# Vorlage_ATmega644PA.net
KiCad netlist of a schematic drawn in EAGLE
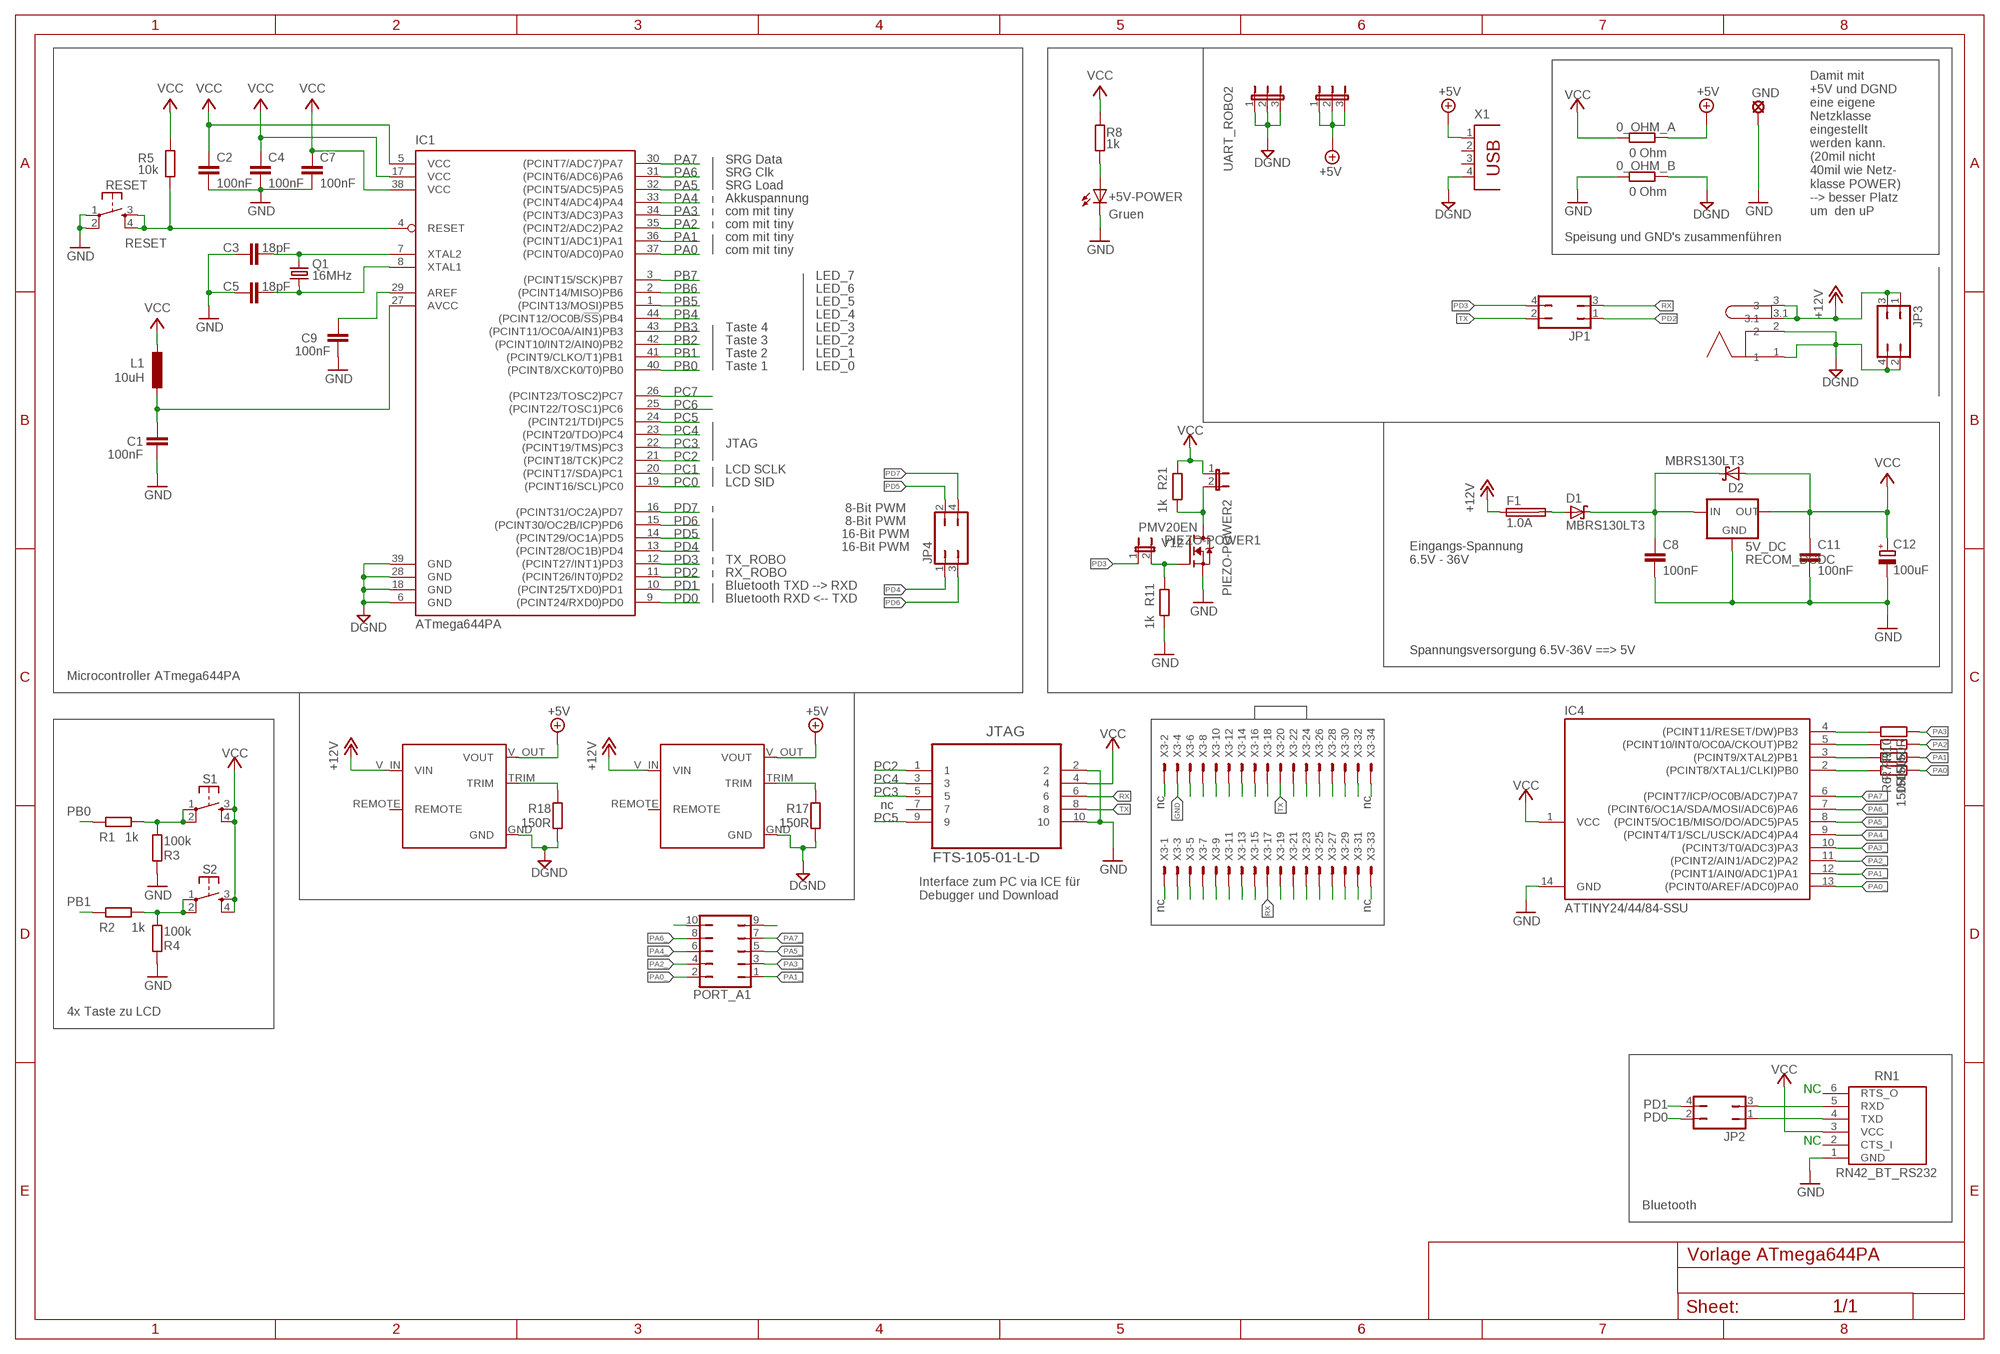
[diagram p0: schematic, sheet 1]

(export (version "E")
  (design (tool "Eeschema 10.0.6"))
  (components
    (comp (ref "+5V-POWER")
      (value "Gruen")
      (footprint "eagle-import:CHIPLED_1206")
      (libsource (lib "eagle-import") (part "LEDCHIPLED_1206"))
    )
    (comp (ref "0_OHM_A")
      (value "0 Ohm")
      (footprint "eagle-import:R0805")
      (libsource (lib "eagle-import") (part "rcl_334_R-EU_R0805"))
    )
    (comp (ref "0_OHM_B")
      (value "0 Ohm")
      (footprint "eagle-import:R0805")
      (libsource (lib "eagle-import") (part "rcl_334_R-EU_R0805"))
    )
    (comp (ref "5V_DC")
      (value "RECOM_DCDC")
      (footprint "eagle-import:RECOM_DCDC")
      (libsource (lib "eagle-import") (part "RECOM_DCDC"))
    )
    (comp (ref "C1")
      (value "100nF")
      (footprint "eagle-import:C0805")
      (libsource (lib "eagle-import") (part "C-EUC0805"))
    )
    (comp (ref "C2")
      (value "100nF")
      (footprint "eagle-import:C0805")
      (libsource (lib "eagle-import") (part "C-EUC0805"))
    )
    (comp (ref "C3")
      (value "18pF")
      (footprint "eagle-import:C0805")
      (libsource (lib "eagle-import") (part "C-EUC0805"))
    )
    (comp (ref "C4")
      (value "100nF")
      (footprint "eagle-import:C0805")
      (libsource (lib "eagle-import") (part "C-EUC0805"))
    )
    (comp (ref "C5")
      (value "18pF")
      (footprint "eagle-import:C0805")
      (libsource (lib "eagle-import") (part "C-EUC0805"))
    )
    (comp (ref "C7")
      (value "100nF")
      (footprint "eagle-import:C0805")
      (libsource (lib "eagle-import") (part "C-EUC0805"))
    )
    (comp (ref "C8")
      (value "100nF")
      (footprint "eagle-import:C0805")
      (libsource (lib "eagle-import") (part "C-EUC0805"))
    )
    (comp (ref "C9")
      (value "100nF")
      (footprint "eagle-import:C0805")
      (libsource (lib "eagle-import") (part "C-EUC0805"))
    )
    (comp (ref "C11")
      (value "100nF")
      (footprint "eagle-import:C0805")
      (libsource (lib "eagle-import") (part "C-EUC0805"))
    )
    (comp (ref "C12")
      (value "100uF")
      (footprint "eagle-import:UD-6,3X5,8_NICHICON")
      (libsource (lib "eagle-import") (part "CPOL-EUUD-6,3X8,8"))
    )
    (comp (ref "D1")
      (value "MBRS130LT3")
      (footprint "eagle-import:SMB")
      (libsource (lib "eagle-import") (part "MBRS130LT3"))
    )
    (comp (ref "D2")
      (value "MBRS130LT3")
      (footprint "eagle-import:SMB")
      (libsource (lib "eagle-import") (part "MBRS130LT3"))
    )
    (comp (ref "F1")
      (value "1.0A")
      (footprint "eagle-import:F1206")
      (libsource (lib "eagle-import") (part "195601206"))
    )
    (comp (ref "GND")
      (value "3.3V")
      (footprint "eagle-import:LSP11")
      (libsource (lib "eagle-import") (part "LSP11"))
    )
    (comp (ref "IC1")
      (value "ATmega644PA")
      (footprint "eagle-import:TQFP44")
      (fields (field (name "MPN") "ATMEGA644PV-10AU"))
      (libsource (lib "eagle-import") (part "ATMEGA644A"))
    )
    (comp (ref "IC4")
      (value "ATTINY24/44/84-SSU")
      (footprint "eagle-import:SOIC14")
      (libsource (lib "eagle-import") (part "ATTINY24/44/84-SSU"))
    )
    (comp (ref "JP1")
      (value "JP2Q")
      (footprint "eagle-import:JP2Q")
      (libsource (lib "eagle-import") (part "JP2Q"))
    )
    (comp (ref "JP2")
      (value "JP2Q")
      (footprint "eagle-import:JP2Q")
      (libsource (lib "eagle-import") (part "JP2Q"))
    )
    (comp (ref "JP3")
      (value "JP2Q")
      (footprint "eagle-import:JP2Q")
      (libsource (lib "eagle-import") (part "JP2Q"))
    )
    (comp (ref "JP4")
      (value "JP2Q")
      (footprint "eagle-import:JP2Q")
      (libsource (lib "eagle-import") (part "JP2Q"))
    )
    (comp (ref "JTAG")
      (value "FTS-105-01-L-D")
      (footprint "eagle-import:SAMTEC_FTS-105-01-L-D")
      (libsource (lib "eagle-import") (part "FTS-105-01-L-D"))
    )
    (comp (ref "L1")
      (value "10uH")
      (footprint "eagle-import:L2825P")
      (libsource (lib "eagle-import") (part "L-EUL2825P"))
    )
    (comp (ref "PIEZO-POWER1")
      (value "JP1E")
      (footprint "eagle-import:JP1")
      (libsource (lib "eagle-import") (part "JP1E"))
    )
    (comp (ref "PIEZO-POWER2")
      (value "JP1E")
      (footprint "eagle-import:JP1")
      (libsource (lib "eagle-import") (part "JP1E"))
    )
    (comp (ref "PORT_A1")
      (value "JP5Q")
      (footprint "eagle-import:JP5Q")
      (libsource (lib "eagle-import") (part "JP5Q"))
    )
    (comp (ref "Q1")
      (value "16MHz")
      (footprint "eagle-import:HC49UP")
      (libsource (lib "eagle-import") (part "CRYSTALHC49UP"))
    )
    (comp (ref "R1")
      (value "1k")
      (footprint "eagle-import:R0805")
      (libsource (lib "eagle-import") (part "rcl_334_R-EU_R0805"))
    )
    (comp (ref "R2")
      (value "1k")
      (footprint "eagle-import:R0805")
      (libsource (lib "eagle-import") (part "rcl_334_R-EU_R0805"))
    )
    (comp (ref "R3")
      (value "100k")
      (footprint "eagle-import:R0805")
      (libsource (lib "eagle-import") (part "rcl_334_R-EU_R0805"))
    )
    (comp (ref "R4")
      (value "100k")
      (footprint "eagle-import:R0805")
      (libsource (lib "eagle-import") (part "rcl_334_R-EU_R0805"))
    )
    (comp (ref "R5")
      (value "10k")
      (footprint "eagle-import:R0805")
      (libsource (lib "eagle-import") (part "rcl_334_R-EU_R0805"))
    )
    (comp (ref "R6")
      (value "150R")
      (footprint "eagle-import:R0805")
      (libsource (lib "eagle-import") (part "rcl_334_R-EU_R0805"))
    )
    (comp (ref "R7")
      (value "150R")
      (footprint "eagle-import:R0805")
      (libsource (lib "eagle-import") (part "rcl_334_R-EU_R0805"))
    )
    (comp (ref "R8")
      (value "1k")
      (footprint "eagle-import:R0805")
      (libsource (lib "eagle-import") (part "rcl_334_R-EU_R0805"))
    )
    (comp (ref "R9")
      (value "150R")
      (footprint "eagle-import:R0805")
      (libsource (lib "eagle-import") (part "rcl_334_R-EU_R0805"))
    )
    (comp (ref "R10")
      (value "150R")
      (footprint "eagle-import:R0805")
      (libsource (lib "eagle-import") (part "rcl_334_R-EU_R0805"))
    )
    (comp (ref "R11")
      (value "1k")
      (footprint "eagle-import:R1206")
      (libsource (lib "eagle-import") (part "R-EU_R1206"))
    )
    (comp (ref "R17")
      (value "150R")
      (footprint "eagle-import:R0805")
      (libsource (lib "eagle-import") (part "rcl_334_R-EU_R0805"))
    )
    (comp (ref "R18")
      (value "150R")
      (footprint "eagle-import:R0805")
      (libsource (lib "eagle-import") (part "rcl_334_R-EU_R0805"))
    )
    (comp (ref "R21")
      (value "1k")
      (footprint "eagle-import:R1206")
      (libsource (lib "eagle-import") (part "R-EU_R1206"))
    )
    (comp (ref "RESET")
      (value "TS42_4PAD")
      (footprint "eagle-import:TS42_4PAD")
      (libsource (lib "eagle-import") (part "TS42_4PAD"))
    )
    (comp (ref "RN1")
      (value "RN42_BT_RS232")
      (footprint "eagle-import:RN42BT_RS232")
      (libsource (lib "eagle-import") (part "RN42_BT_RS232"))
    )
    (comp (ref "S1")
      (value "TS42_4PAD")
      (footprint "eagle-import:TS42_4PAD")
      (libsource (lib "eagle-import") (part "TS42_4PAD"))
    )
    (comp (ref "S2")
      (value "TS42_4PAD")
      (footprint "eagle-import:TS42_4PAD")
      (libsource (lib "eagle-import") (part "TS42_4PAD"))
    )
    (comp (ref "U$1")
      (value "BUCHSE")
      (footprint "eagle-import:BUCHSE")
      (libsource (lib "eagle-import") (part "BUCHSE"))
    )
    (comp (ref "U$2")
      (value "DCDC")
      (footprint "eagle-import:1X2,3_2.54MM")
      (libsource (lib "eagle-import") (part "DCDC"))
    )
    (comp (ref "U$3")
      (value "DCDC")
      (footprint "eagle-import:1X2,3_2.54MM")
      (libsource (lib "eagle-import") (part "DCDC"))
    )
    (comp (ref "UART_ROBO1")
      (value "JP2E")
      (footprint "eagle-import:JP2")
      (libsource (lib "eagle-import") (part "JP2E"))
    )
    (comp (ref "UART_ROBO2")
      (value "JP2E")
      (footprint "eagle-import:JP2")
      (libsource (lib "eagle-import") (part "JP2E"))
    )
    (comp (ref "V12")
      (value "PMV20EN")
      (footprint "eagle-import:SOT23")
      (libsource (lib "eagle-import") (part "BSS138"))
    )
    (comp (ref "X1")
      (value "PN87520")
      (footprint "eagle-import:PN87520")
      (libsource (lib "eagle-import") (part "PN87520"))
    )
    (comp (ref "X3")
      (value "87758-3416")
      (footprint "eagle-import:87758-3416")
      (fields (field (name "MF") "MOLEX"))
      (libsource (lib "eagle-import") (part "87758-3416"))
    )
  )
  (nets
    (net (code "1") (name "+5V") (class "Default")
      (node (ref "0_OHM_A") (pin "2") (pinfunction "2_2") (pintype "passive"))
      (node (ref "U$2") (pin "V_OUT") (pinfunction "VOUT_V_OUT") (pintype "bidirectional"))
      (node (ref "U$3") (pin "V_OUT") (pinfunction "VOUT_V_OUT") (pintype "bidirectional"))
      (node (ref "UART_ROBO1") (pin "1") (pinfunction "1_1") (pintype "passive"))
      (node (ref "UART_ROBO1") (pin "2") (pinfunction "2_2") (pintype "passive"))
      (node (ref "UART_ROBO1") (pin "3") (pinfunction "3_3") (pintype "passive"))
      (node (ref "X1") (pin "1") (pinfunction "1_1") (pintype "passive"))
    )
    (net (code "2") (name "+12V") (class "Default")
      (node (ref "F1") (pin "1") (pinfunction "1_1") (pintype "passive"))
      (node (ref "JP3") (pin "1") (pinfunction "1_1") (pintype "passive"))
      (node (ref "JP3") (pin "3") (pinfunction "3_3") (pintype "passive"))
      (node (ref "U$1") (pin "3") (pinfunction "3_3") (pintype "bidirectional"))
      (node (ref "U$1") (pin "3.1") (pinfunction "3.1_3.1") (pintype "bidirectional"))
      (node (ref "U$2") (pin "V_IN") (pinfunction "VIN_V_IN") (pintype "bidirectional"))
      (node (ref "U$3") (pin "V_IN") (pinfunction "VIN_V_IN") (pintype "bidirectional"))
    )
    (net (code "3") (name "/PA4") (class "Default")
      (node (ref "IC1") (pin "33") (pinfunction "(PCINT4/ADC4)PA4_33") (pintype "bidirectional"))
    )
    (net (code "4") (name "/PA5") (class "Default")
      (node (ref "IC1") (pin "32") (pinfunction "(PCINT5/ADC5)PA5_32") (pintype "bidirectional"))
    )
    (net (code "5") (name "/PA6") (class "Default")
      (node (ref "IC1") (pin "31") (pinfunction "(PCINT6/ADC6)PA6_31") (pintype "bidirectional"))
    )
    (net (code "6") (name "/PA7") (class "Default")
      (node (ref "IC1") (pin "30") (pinfunction "(PCINT7/ADC7)PA7_30") (pintype "bidirectional"))
    )
    (net (code "7") (name "/PB0") (class "Default")
      (node (ref "IC1") (pin "40") (pinfunction "(PCINT8/XCK0/T0)PB0_40") (pintype "bidirectional"))
      (node (ref "R1") (pin "1") (pinfunction "1_1") (pintype "passive"))
    )
    (net (code "8") (name "/PB1") (class "Default")
      (node (ref "IC1") (pin "41") (pinfunction "(PCINT9/CLKO/T1)PB1_41") (pintype "bidirectional"))
      (node (ref "R2") (pin "1") (pinfunction "1_1") (pintype "passive"))
    )
    (net (code "9") (name "/PB2") (class "Default")
      (node (ref "IC1") (pin "42") (pinfunction "(PCINT10/INT2/AIN0)PB2_42") (pintype "bidirectional"))
    )
    (net (code "10") (name "/PB3") (class "Default")
      (node (ref "IC1") (pin "43") (pinfunction "(PCINT11/OC0A/AIN1)PB3_43") (pintype "bidirectional"))
    )
    (net (code "11") (name "/PB4") (class "Default")
      (node (ref "IC1") (pin "44") (pinfunction "(PCINT12/OC0B/~{SS})PB4_44") (pintype "bidirectional"))
    )
    (net (code "12") (name "/PB5") (class "Default")
      (node (ref "IC1") (pin "1") (pinfunction "(PCINT13/MOSI)PB5_1") (pintype "bidirectional"))
    )
    (net (code "13") (name "/PB6") (class "Default")
      (node (ref "IC1") (pin "2") (pinfunction "(PCINT14/MISO)PB6_2") (pintype "bidirectional"))
    )
    (net (code "14") (name "/PB7") (class "Default")
      (node (ref "IC1") (pin "3") (pinfunction "(PCINT15/SCK)PB7_3") (pintype "bidirectional"))
    )
    (net (code "15") (name "/PC0") (class "Default")
      (node (ref "IC1") (pin "19") (pinfunction "(PCINT16/SCL)PC0_19") (pintype "output"))
    )
    (net (code "16") (name "/PC1") (class "Default")
      (node (ref "IC1") (pin "20") (pinfunction "(PCINT17/SDA)PC1_20") (pintype "output"))
    )
    (net (code "17") (name "/PC2") (class "Default")
      (node (ref "IC1") (pin "21") (pinfunction "(PCINT18/TCK)PC2_21") (pintype "output"))
      (node (ref "JTAG") (pin "1") (pinfunction "1_1") (pintype "passive"))
    )
    (net (code "18") (name "/PC3") (class "Default")
      (node (ref "IC1") (pin "22") (pinfunction "(PCINT19/TMS)PC3_22") (pintype "output"))
      (node (ref "JTAG") (pin "5") (pinfunction "5_5") (pintype "passive"))
    )
    (net (code "19") (name "/PC4") (class "Default")
      (node (ref "IC1") (pin "23") (pinfunction "(PCINT20/TDO)PC4_23") (pintype "output"))
      (node (ref "JTAG") (pin "3") (pinfunction "3_3") (pintype "passive"))
    )
    (net (code "20") (name "/PC5") (class "Default")
      (node (ref "IC1") (pin "24") (pinfunction "(PCINT21/TDI)PC5_24") (pintype "output"))
      (node (ref "JTAG") (pin "9") (pinfunction "9_9") (pintype "passive"))
    )
    (net (code "21") (name "/PC6") (class "Default")
      (node (ref "IC1") (pin "25") (pinfunction "(PCINT22/TOSC1)PC6_25") (pintype "output"))
    )
    (net (code "22") (name "/PC7") (class "Default")
      (node (ref "IC1") (pin "26") (pinfunction "(PCINT23/TOSC2)PC7_26") (pintype "output"))
    )
    (net (code "23") (name "/PD0") (class "Default")
      (node (ref "IC1") (pin "9") (pinfunction "(PCINT24/RXD0)PD0_9") (pintype "bidirectional"))
      (node (ref "JP2") (pin "2") (pinfunction "2_2") (pintype "passive"))
    )
    (net (code "24") (name "/PD1") (class "Default")
      (node (ref "IC1") (pin "10") (pinfunction "(PCINT25/TXD0)PD1_10") (pintype "bidirectional"))
      (node (ref "JP2") (pin "4") (pinfunction "4_4") (pintype "passive"))
    )
    (net (code "25") (name "/RESET") (class "Default")
      (node (ref "IC1") (pin "4") (pinfunction "RESET_4") (pintype "input"))
      (node (ref "R5") (pin "1") (pinfunction "1_1") (pintype "passive"))
      (node (ref "RESET") (pin "3") (pinfunction "3_3") (pintype "passive"))
      (node (ref "RESET") (pin "4") (pinfunction "4_4") (pintype "passive"))
    )
    (net (code "26") (name "DGND") (class "Default")
      (node (ref "0_OHM_B") (pin "2") (pinfunction "2_2") (pintype "passive"))
      (node (ref "IC1") (pin "18") (pinfunction "GND_18") (pintype "power_in"))
      (node (ref "IC1") (pin "28") (pinfunction "GND_28") (pintype "power_in"))
      (node (ref "IC1") (pin "39") (pinfunction "GND_39") (pintype "power_in"))
      (node (ref "IC1") (pin "6") (pinfunction "GND_6") (pintype "power_in"))
      (node (ref "JP3") (pin "2") (pinfunction "2_2") (pintype "passive"))
      (node (ref "JP3") (pin "4") (pinfunction "4_4") (pintype "passive"))
      (node (ref "R17") (pin "1") (pinfunction "1_1") (pintype "passive"))
      (node (ref "R18") (pin "1") (pinfunction "1_1") (pintype "passive"))
      (node (ref "U$1") (pin "1") (pinfunction "1_1") (pintype "bidirectional"))
      (node (ref "U$1") (pin "2") (pinfunction "2_2") (pintype "bidirectional"))
      (node (ref "U$2") (pin "GND") (pinfunction "GND_GND") (pintype "bidirectional"))
      (node (ref "U$3") (pin "GND") (pinfunction "GND_GND") (pintype "bidirectional"))
      (node (ref "UART_ROBO2") (pin "1") (pinfunction "1_1") (pintype "passive"))
      (node (ref "UART_ROBO2") (pin "2") (pinfunction "2_2") (pintype "passive"))
      (node (ref "UART_ROBO2") (pin "3") (pinfunction "3_3") (pintype "passive"))
      (node (ref "X1") (pin "4") (pinfunction "4_4") (pintype "passive"))
    )
    (net (code "27") (name "GND") (class "Default")
      (node (ref "+5V-POWER") (pin "C") (pinfunction "C_C") (pintype "passive"))
      (node (ref "0_OHM_B") (pin "1") (pinfunction "1_1") (pintype "passive"))
      (node (ref "5V_DC") (pin "GND") (pinfunction "GND_GND") (pintype "input"))
      (node (ref "C1") (pin "1") (pinfunction "1_1") (pintype "passive"))
      (node (ref "C11") (pin "2") (pinfunction "2_2") (pintype "passive"))
      (node (ref "C12") (pin "-") (pinfunction "-_-") (pintype "passive"))
      (node (ref "C2") (pin "2") (pinfunction "2_2") (pintype "passive"))
      (node (ref "C3") (pin "1") (pinfunction "1_1") (pintype "passive"))
      (node (ref "C4") (pin "2") (pinfunction "2_2") (pintype "passive"))
      (node (ref "C5") (pin "2") (pinfunction "2_2") (pintype "passive"))
      (node (ref "C7") (pin "2") (pinfunction "2_2") (pintype "passive"))
      (node (ref "C8") (pin "2") (pinfunction "2_2") (pintype "passive"))
      (node (ref "C9") (pin "1") (pinfunction "1_1") (pintype "passive"))
      (node (ref "GND") (pin "MP") (pinfunction "MP_MP") (pintype "passive"))
      (node (ref "IC4") (pin "14") (pinfunction "GND_14") (pintype "power_in"))
      (node (ref "JTAG") (pin "10") (pinfunction "10_10") (pintype "passive"))
      (node (ref "JTAG") (pin "2") (pinfunction "2_2") (pintype "passive"))
      (node (ref "R11") (pin "2") (pinfunction "2_2") (pintype "passive"))
      (node (ref "R3") (pin "1") (pinfunction "1_1") (pintype "passive"))
      (node (ref "R4") (pin "1") (pinfunction "1_1") (pintype "passive"))
      (node (ref "RESET") (pin "1") (pinfunction "1_1") (pintype "passive"))
      (node (ref "RESET") (pin "2") (pinfunction "2_2") (pintype "passive"))
      (node (ref "RN1") (pin "1") (pinfunction "GND_1") (pintype "bidirectional"))
      (node (ref "V12") (pin "2") (pinfunction "S_2") (pintype "passive"))
      (node (ref "X3") (pin "4") (pinfunction "S_4") (pintype "passive"))
    )
    (net (code "28") (name "Net-(+5V-POWER-PadA)") (class "Default")
      (node (ref "+5V-POWER") (pin "A") (pinfunction "A_A") (pintype "passive"))
      (node (ref "R8") (pin "1") (pinfunction "1_1") (pintype "passive"))
    )
    (net (code "29") (name "Net-(5V_DC-PadIN)") (class "Default")
      (node (ref "5V_DC") (pin "IN") (pinfunction "IN_IN") (pintype "input"))
      (node (ref "C8") (pin "1") (pinfunction "1_1") (pintype "passive"))
      (node (ref "D1") (pin "C") (pinfunction "C_C") (pintype "passive"))
      (node (ref "D2") (pin "C") (pinfunction "C_C") (pintype "passive"))
    )
    (net (code "30") (name "Net-(D1-PadA)") (class "Default")
      (node (ref "D1") (pin "A") (pinfunction "A_A") (pintype "passive"))
      (node (ref "F1") (pin "2") (pinfunction "2_2") (pintype "passive"))
    )
    (net (code "31") (name "Net-(IC1-AREF)") (class "Default")
      (node (ref "C9") (pin "2") (pinfunction "2_2") (pintype "passive"))
      (node (ref "IC1") (pin "29") (pinfunction "AREF_29") (pintype "passive"))
    )
    (net (code "32") (name "Net-(IC1-AVCC)") (class "Default")
      (node (ref "C1") (pin "2") (pinfunction "2_2") (pintype "passive"))
      (node (ref "IC1") (pin "27") (pinfunction "AVCC_27") (pintype "passive"))
      (node (ref "L1") (pin "2") (pinfunction "2_2") (pintype "passive"))
    )
    (net (code "33") (name "Net-(IC1-XTAL1)") (class "Default")
      (node (ref "C5") (pin "1") (pinfunction "1_1") (pintype "passive"))
      (node (ref "IC1") (pin "8") (pinfunction "XTAL1_8") (pintype "bidirectional"))
      (node (ref "Q1") (pin "1") (pinfunction "1_1") (pintype "passive"))
    )
    (net (code "34") (name "Net-(IC1-XTAL2)") (class "Default")
      (node (ref "C3") (pin "2") (pinfunction "2_2") (pintype "passive"))
      (node (ref "IC1") (pin "7") (pinfunction "XTAL2_7") (pintype "bidirectional"))
      (node (ref "Q1") (pin "2") (pinfunction "2_2") (pintype "passive"))
    )
    (net (code "35") (name "Net-(IC4-(PCINT8{slash}XTAL1{slash}CLKI)PB0)") (class "Default")
      (node (ref "IC4") (pin "2") (pinfunction "(PCINT8/XTAL1/CLKI)PB0_2") (pintype "bidirectional"))
      (node (ref "R6") (pin "2") (pinfunction "2_2") (pintype "passive"))
    )
    (net (code "36") (name "Net-(IC4-(PCINT9{slash}XTAL2)PB1)") (class "Default")
      (node (ref "IC4") (pin "3") (pinfunction "(PCINT9/XTAL2)PB1_3") (pintype "bidirectional"))
      (node (ref "R7") (pin "2") (pinfunction "2_2") (pintype "passive"))
    )
    (net (code "37") (name "Net-(IC4-(PCINT10{slash}INT0{slash}OC0A{slash}CKOUT)PB2)") (class "Default")
      (node (ref "IC4") (pin "5") (pinfunction "(PCINT10/INT0/OC0A/CKOUT)PB2_5") (pintype "bidirectional"))
      (node (ref "R9") (pin "2") (pinfunction "2_2") (pintype "passive"))
    )
    (net (code "38") (name "Net-(IC4-(PCINT11{slash}RESET{slash}DW)PB3)") (class "Default")
      (node (ref "IC4") (pin "4") (pinfunction "(PCINT11/RESET/DW)PB3_4") (pintype "bidirectional"))
      (node (ref "R10") (pin "2") (pinfunction "2_2") (pintype "passive"))
    )
    (net (code "39") (name "Net-(R1-Pad2)") (class "Default")
      (node (ref "R1") (pin "2") (pinfunction "2_2") (pintype "passive"))
      (node (ref "R3") (pin "2") (pinfunction "2_2") (pintype "passive"))
      (node (ref "S1") (pin "1") (pinfunction "1_1") (pintype "passive"))
      (node (ref "S1") (pin "2") (pinfunction "2_2") (pintype "passive"))
    )
    (net (code "40") (name "Net-(R2-Pad2)") (class "Default")
      (node (ref "R2") (pin "2") (pinfunction "2_2") (pintype "passive"))
      (node (ref "R4") (pin "2") (pinfunction "2_2") (pintype "passive"))
      (node (ref "S2") (pin "1") (pinfunction "1_1") (pintype "passive"))
      (node (ref "S2") (pin "2") (pinfunction "2_2") (pintype "passive"))
    )
    (net (code "41") (name "Net-(R17-Pad2)") (class "Default")
      (node (ref "R17") (pin "2") (pinfunction "2_2") (pintype "passive"))
      (node (ref "U$2") (pin "TRIM") (pinfunction "TRIM_TRIM") (pintype "bidirectional"))
    )
    (net (code "42") (name "Net-(R18-Pad2)") (class "Default")
      (node (ref "R18") (pin "2") (pinfunction "2_2") (pintype "passive"))
      (node (ref "U$3") (pin "TRIM") (pinfunction "TRIM_TRIM") (pintype "bidirectional"))
    )
    (net (code "43") (name "Net-(RN1-RXD)") (class "Default")
      (node (ref "JP2") (pin "3") (pinfunction "3_3") (pintype "passive"))
      (node (ref "RN1") (pin "5") (pinfunction "RXD_5") (pintype "bidirectional"))
    )
    (net (code "44") (name "Net-(RN1-TXD)") (class "Default")
      (node (ref "JP2") (pin "1") (pinfunction "1_1") (pintype "passive"))
      (node (ref "RN1") (pin "4") (pinfunction "TXD_4") (pintype "bidirectional"))
    )
    (net (code "45") (name "Net-(V12-D)") (class "Default")
      (node (ref "PIEZO-POWER2") (pin "2") (pinfunction "2_2") (pintype "passive"))
      (node (ref "R21") (pin "2") (pinfunction "2_2") (pintype "passive"))
      (node (ref "V12") (pin "3") (pinfunction "D_3") (pintype "passive"))
    )
    (net (code "46") (name "Net-(V12-G)") (class "Default")
      (node (ref "PIEZO-POWER1") (pin "2") (pinfunction "2_2") (pintype "passive"))
      (node (ref "R11") (pin "1") (pinfunction "1_1") (pintype "passive"))
      (node (ref "V12") (pin "1") (pinfunction "G_1") (pintype "passive"))
    )
    (net (code "47") (name "PA0") (class "Default")
      (node (ref "IC1") (pin "37") (pinfunction "(PCINT0/ADC0)PA0_37") (pintype "bidirectional"))
      (node (ref "R6") (pin "1") (pinfunction "1_1") (pintype "passive"))
    )
    (net (code "48") (name "PA0_") (class "Default")
      (node (ref "IC4") (pin "13") (pinfunction "(PCINT0/AREF/ADC0)PA0_13") (pintype "bidirectional"))
      (node (ref "PORT_A1") (pin "2") (pinfunction "2_2") (pintype "passive"))
    )
    (net (code "49") (name "PA1") (class "Default")
      (node (ref "IC1") (pin "36") (pinfunction "(PCINT1/ADC1)PA1_36") (pintype "bidirectional"))
      (node (ref "R7") (pin "1") (pinfunction "1_1") (pintype "passive"))
    )
    (net (code "50") (name "PA1_") (class "Default")
      (node (ref "IC4") (pin "12") (pinfunction "(PCINT1/AIN0/ADC1)PA1_12") (pintype "bidirectional"))
      (node (ref "PORT_A1") (pin "1") (pinfunction "1_1") (pintype "passive"))
    )
    (net (code "51") (name "PA2") (class "Default")
      (node (ref "IC1") (pin "35") (pinfunction "(PCINT2/ADC2)PA2_35") (pintype "bidirectional"))
      (node (ref "R9") (pin "1") (pinfunction "1_1") (pintype "passive"))
    )
    (net (code "52") (name "PA2_") (class "Default")
      (node (ref "IC4") (pin "11") (pinfunction "(PCINT2/AIN1/ADC2)PA2_11") (pintype "bidirectional"))
      (node (ref "PORT_A1") (pin "4") (pinfunction "4_4") (pintype "passive"))
    )
    (net (code "53") (name "PA3") (class "Default")
      (node (ref "IC1") (pin "34") (pinfunction "(PCINT3/ADC3)PA3_34") (pintype "bidirectional"))
      (node (ref "R10") (pin "1") (pinfunction "1_1") (pintype "passive"))
    )
    (net (code "54") (name "PA3_") (class "Default")
      (node (ref "IC4") (pin "10") (pinfunction "(PCINT3/T0/ADC3)PA3_10") (pintype "bidirectional"))
      (node (ref "PORT_A1") (pin "3") (pinfunction "3_3") (pintype "passive"))
    )
    (net (code "55") (name "PA4_") (class "Default")
      (node (ref "IC4") (pin "9") (pinfunction "(PCINT4/T1/SCL/USCK/ADC4)PA4_9") (pintype "bidirectional"))
      (node (ref "PORT_A1") (pin "6") (pinfunction "6_6") (pintype "passive"))
    )
    (net (code "56") (name "PA5_") (class "Default")
      (node (ref "IC4") (pin "8") (pinfunction "(PCINT5/OC1B/MISO/DO/ADC5)PA5_8") (pintype "bidirectional"))
      (node (ref "PORT_A1") (pin "5") (pinfunction "5_5") (pintype "passive"))
    )
    (net (code "57") (name "PA6_") (class "Default")
      (node (ref "IC4") (pin "7") (pinfunction "(PCINT6/OC1A/SDA/MOSI/ADC6)PA6_7") (pintype "bidirectional"))
      (node (ref "PORT_A1") (pin "8") (pinfunction "8_8") (pintype "passive"))
    )
    (net (code "58") (name "PA7_") (class "Default")
      (node (ref "IC4") (pin "6") (pinfunction "(PCINT7/ICP/OC0B/ADC7)PA7_6") (pintype "bidirectional"))
      (node (ref "PORT_A1") (pin "7") (pinfunction "7_7") (pintype "passive"))
    )
    (net (code "59") (name "PD2") (class "Default")
      (node (ref "IC1") (pin "11") (pinfunction "(PCINT26/INT0)PD2_11") (pintype "bidirectional"))
      (node (ref "JP1") (pin "1") (pinfunction "1_1") (pintype "passive"))
    )
    (net (code "60") (name "PD3") (class "Default")
      (node (ref "IC1") (pin "12") (pinfunction "(PCINT27/INT1)PD3_12") (pintype "bidirectional"))
      (node (ref "JP1") (pin "4") (pinfunction "4_4") (pintype "passive"))
      (node (ref "PIEZO-POWER1") (pin "1") (pinfunction "1_1") (pintype "passive"))
    )
    (net (code "61") (name "PD4") (class "Default")
      (node (ref "IC1") (pin "13") (pinfunction "(PCINT28/OC1B)PD4_13") (pintype "bidirectional"))
      (node (ref "JP4") (pin "1") (pinfunction "1_1") (pintype "passive"))
    )
    (net (code "62") (name "PD5") (class "Default")
      (node (ref "IC1") (pin "14") (pinfunction "(PCINT29/OC1A)PD5_14") (pintype "bidirectional"))
      (node (ref "JP4") (pin "2") (pinfunction "2_2") (pintype "passive"))
    )
    (net (code "63") (name "PD6") (class "Default")
      (node (ref "IC1") (pin "15") (pinfunction "(PCINT30/OC2B/ICP)PD6_15") (pintype "bidirectional"))
      (node (ref "JP4") (pin "3") (pinfunction "3_3") (pintype "passive"))
    )
    (net (code "64") (name "PD7") (class "Default")
      (node (ref "IC1") (pin "16") (pinfunction "(PCINT31/OC2A)PD7_16") (pintype "bidirectional"))
      (node (ref "JP4") (pin "4") (pinfunction "4_4") (pintype "passive"))
    )
    (net (code "65") (name "RX") (class "Default")
      (node (ref "JP1") (pin "3") (pinfunction "3_3") (pintype "passive"))
      (node (ref "JTAG") (pin "6") (pinfunction "6_6") (pintype "passive"))
      (node (ref "X3") (pin "17") (pinfunction "S_17") (pintype "passive"))
    )
    (net (code "66") (name "TX") (class "Default")
      (node (ref "JP1") (pin "2") (pinfunction "2_2") (pintype "passive"))
      (node (ref "JTAG") (pin "8") (pinfunction "8_8") (pintype "passive"))
      (node (ref "X3") (pin "20") (pinfunction "S_20") (pintype "passive"))
    )
    (net (code "67") (name "VCC") (class "Default")
      (node (ref "0_OHM_A") (pin "1") (pinfunction "1_1") (pintype "passive"))
      (node (ref "5V_DC") (pin "OUT") (pinfunction "OUT_OUT") (pintype "passive"))
      (node (ref "C11") (pin "1") (pinfunction "1_1") (pintype "passive"))
      (node (ref "C12") (pin "+") (pinfunction "+_+") (pintype "passive"))
      (node (ref "C2") (pin "1") (pinfunction "1_1") (pintype "passive"))
      (node (ref "C4") (pin "1") (pinfunction "1_1") (pintype "passive"))
      (node (ref "C7") (pin "1") (pinfunction "1_1") (pintype "passive"))
      (node (ref "D2") (pin "A") (pinfunction "A_A") (pintype "passive"))
      (node (ref "IC1") (pin "17") (pinfunction "VCC_17") (pintype "power_in"))
      (node (ref "IC1") (pin "38") (pinfunction "VCC_38") (pintype "power_in"))
      (node (ref "IC1") (pin "5") (pinfunction "VCC_5") (pintype "power_in"))
      (node (ref "IC4") (pin "1") (pinfunction "VCC_1") (pintype "power_in"))
      (node (ref "JTAG") (pin "4") (pinfunction "4_4") (pintype "passive"))
      (node (ref "L1") (pin "1") (pinfunction "1_1") (pintype "passive"))
      (node (ref "PIEZO-POWER2") (pin "1") (pinfunction "1_1") (pintype "passive"))
      (node (ref "R21") (pin "1") (pinfunction "1_1") (pintype "passive"))
      (node (ref "R5") (pin "2") (pinfunction "2_2") (pintype "passive"))
      (node (ref "R8") (pin "2") (pinfunction "2_2") (pintype "passive"))
      (node (ref "RN1") (pin "3") (pinfunction "VCC_3") (pintype "bidirectional"))
      (node (ref "S1") (pin "3") (pinfunction "3_3") (pintype "passive"))
      (node (ref "S1") (pin "4") (pinfunction "4_4") (pintype "passive"))
      (node (ref "S2") (pin "3") (pinfunction "3_3") (pintype "passive"))
      (node (ref "S2") (pin "4") (pinfunction "4_4") (pintype "passive"))
    )
    (net (code "68") (name "unconnected-(JTAG-Pad7)") (class "Default")
      (node (ref "JTAG") (pin "7") (pinfunction "7_7") (pintype "passive"))
    )
    (net (code "69") (name "unconnected-(PORT_A1-Pad9)") (class "Default")
      (node (ref "PORT_A1") (pin "9") (pinfunction "9_9") (pintype "passive"))
    )
    (net (code "70") (name "unconnected-(PORT_A1-Pad10)") (class "Default")
      (node (ref "PORT_A1") (pin "10") (pinfunction "10_10") (pintype "passive"))
    )
    (net (code "71") (name "unconnected-(RN1-CTS_I-Pad2)") (class "Default")
      (node (ref "RN1") (pin "2") (pinfunction "CTS_I_2") (pintype "bidirectional"))
    )
    (net (code "72") (name "unconnected-(RN1-RTS_O-Pad6)") (class "Default")
      (node (ref "RN1") (pin "6") (pinfunction "RTS_O_6") (pintype "bidirectional"))
    )
    (net (code "73") (name "unconnected-(U$2-PadREMOTE)") (class "Default")
      (node (ref "U$2") (pin "REMOTE") (pinfunction "REMOTE_REMOTE") (pintype "bidirectional"))
    )
    (net (code "74") (name "unconnected-(U$3-PadREMOTE)") (class "Default")
      (node (ref "U$3") (pin "REMOTE") (pinfunction "REMOTE_REMOTE") (pintype "bidirectional"))
    )
    (net (code "75") (name "unconnected-(X1-Pad2)") (class "Default")
      (node (ref "X1") (pin "2") (pinfunction "2_2") (pintype "passive"))
    )
    (net (code "76") (name "unconnected-(X1-Pad3)") (class "Default")
      (node (ref "X1") (pin "3") (pinfunction "3_3") (pintype "passive"))
    )
    (net (code "77") (name "unconnected-(X3A-S-Pad1)") (class "Default")
      (node (ref "X3") (pin "1") (pinfunction "S_1") (pintype "passive"))
    )
    (net (code "78") (name "unconnected-(X3AA-S-Pad33)") (class "Default")
      (node (ref "X3") (pin "33") (pinfunction "S_33") (pintype "passive"))
    )
    (net (code "79") (name "unconnected-(X3AB-S-Pad34)") (class "Default")
      (node (ref "X3") (pin "34") (pinfunction "S_34") (pintype "passive"))
    )
    (net (code "80") (name "unconnected-(X3AD-S-Pad5)") (class "Default")
      (node (ref "X3") (pin "5") (pinfunction "S_5") (pintype "passive"))
    )
    (net (code "81") (name "unconnected-(X3AE-S-Pad6)") (class "Default")
      (node (ref "X3") (pin "6") (pinfunction "S_6") (pintype "passive"))
    )
    (net (code "82") (name "unconnected-(X3AF-S-Pad7)") (class "Default")
      (node (ref "X3") (pin "7") (pinfunction "S_7") (pintype "passive"))
    )
    (net (code "83") (name "unconnected-(X3AG-S-Pad8)") (class "Default")
      (node (ref "X3") (pin "8") (pinfunction "S_8") (pintype "passive"))
    )
    (net (code "84") (name "unconnected-(X3AH-S-Pad9)") (class "Default")
      (node (ref "X3") (pin "9") (pinfunction "S_9") (pintype "passive"))
    )
    (net (code "85") (name "unconnected-(X3B-S-Pad10)") (class "Default")
      (node (ref "X3") (pin "10") (pinfunction "S_10") (pintype "passive"))
    )
    (net (code "86") (name "unconnected-(X3C-S-Pad11)") (class "Default")
      (node (ref "X3") (pin "11") (pinfunction "S_11") (pintype "passive"))
    )
    (net (code "87") (name "unconnected-(X3D-S-Pad12)") (class "Default")
      (node (ref "X3") (pin "12") (pinfunction "S_12") (pintype "passive"))
    )
    (net (code "88") (name "unconnected-(X3E-S-Pad13)") (class "Default")
      (node (ref "X3") (pin "13") (pinfunction "S_13") (pintype "passive"))
    )
    (net (code "89") (name "unconnected-(X3F-S-Pad14)") (class "Default")
      (node (ref "X3") (pin "14") (pinfunction "S_14") (pintype "passive"))
    )
    (net (code "90") (name "unconnected-(X3G-S-Pad15)") (class "Default")
      (node (ref "X3") (pin "15") (pinfunction "S_15") (pintype "passive"))
    )
    (net (code "91") (name "unconnected-(X3H-S-Pad16)") (class "Default")
      (node (ref "X3") (pin "16") (pinfunction "S_16") (pintype "passive"))
    )
    (net (code "92") (name "unconnected-(X3J-S-Pad18)") (class "Default")
      (node (ref "X3") (pin "18") (pinfunction "S_18") (pintype "passive"))
    )
    (net (code "93") (name "unconnected-(X3K-S-Pad19)") (class "Default")
      (node (ref "X3") (pin "19") (pinfunction "S_19") (pintype "passive"))
    )
    (net (code "94") (name "unconnected-(X3L-S-Pad2)") (class "Default")
      (node (ref "X3") (pin "2") (pinfunction "S_2") (pintype "passive"))
    )
    (net (code "95") (name "unconnected-(X3N-S-Pad21)") (class "Default")
      (node (ref "X3") (pin "21") (pinfunction "S_21") (pintype "passive"))
    )
    (net (code "96") (name "unconnected-(X3O-S-Pad22)") (class "Default")
      (node (ref "X3") (pin "22") (pinfunction "S_22") (pintype "passive"))
    )
    (net (code "97") (name "unconnected-(X3P-S-Pad23)") (class "Default")
      (node (ref "X3") (pin "23") (pinfunction "S_23") (pintype "passive"))
    )
    (net (code "98") (name "unconnected-(X3Q-S-Pad24)") (class "Default")
      (node (ref "X3") (pin "24") (pinfunction "S_24") (pintype "passive"))
    )
    (net (code "99") (name "unconnected-(X3R-S-Pad25)") (class "Default")
      (node (ref "X3") (pin "25") (pinfunction "S_25") (pintype "passive"))
    )
    (net (code "100") (name "unconnected-(X3S-S-Pad26)") (class "Default")
      (node (ref "X3") (pin "26") (pinfunction "S_26") (pintype "passive"))
    )
    (net (code "101") (name "unconnected-(X3T-S-Pad27)") (class "Default")
      (node (ref "X3") (pin "27") (pinfunction "S_27") (pintype "passive"))
    )
    (net (code "102") (name "unconnected-(X3U-S-Pad28)") (class "Default")
      (node (ref "X3") (pin "28") (pinfunction "S_28") (pintype "passive"))
    )
    (net (code "103") (name "unconnected-(X3V-S-Pad29)") (class "Default")
      (node (ref "X3") (pin "29") (pinfunction "S_29") (pintype "passive"))
    )
    (net (code "104") (name "unconnected-(X3W-S-Pad3)") (class "Default")
      (node (ref "X3") (pin "3") (pinfunction "S_3") (pintype "passive"))
    )
    (net (code "105") (name "unconnected-(X3X-S-Pad30)") (class "Default")
      (node (ref "X3") (pin "30") (pinfunction "S_30") (pintype "passive"))
    )
    (net (code "106") (name "unconnected-(X3Y-S-Pad31)") (class "Default")
      (node (ref "X3") (pin "31") (pinfunction "S_31") (pintype "passive"))
    )
    (net (code "107") (name "unconnected-(X3Z-S-Pad32)") (class "Default")
      (node (ref "X3") (pin "32") (pinfunction "S_32") (pintype "passive"))
    )
  )
)
